# split2.net
KiCad netlist of a schematic drawn in Altium Designer
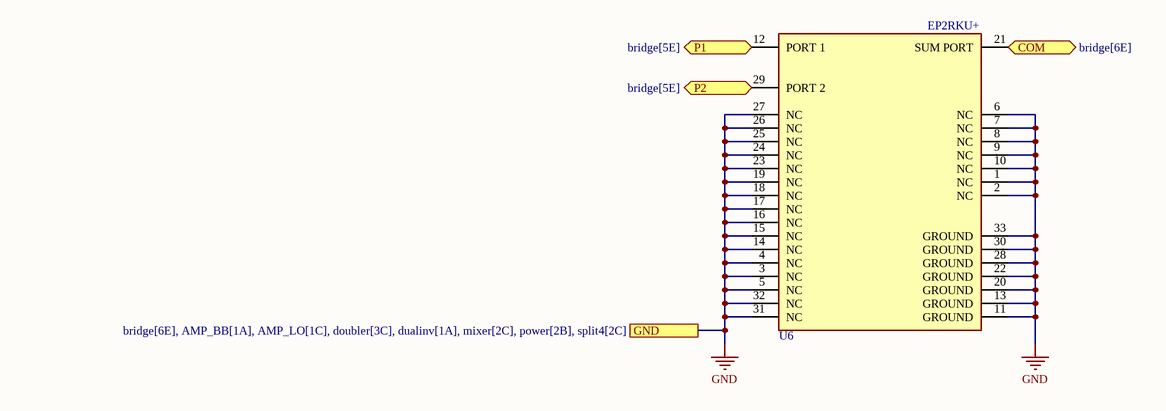
[diagram p0: split2.SchDoc]

(export (version "E")
  (design (tool "Eeschema 10.0.6"))
  (components
    (comp (ref "U6")
      (value "EP2RKU+")
      (footprint "EP2RKU+")
      (description "2 Ways MMIC Power Splitter, DC - 18000 MHz, 50Ω")
      (fields (field (name "MANUFACTURER") "Mini-Circuits"))
      (libsource (lib "FullyDigital") (part "EP2RKU+"))
    )
  )
  (nets
    (net (code "1") (name "/COM") (class "Default")
      (node (ref "U6") (pin "21") (pinfunction "SUM_PORT_21") (pintype "passive"))
    )
    (net (code "2") (name "/P1") (class "Default")
      (node (ref "U6") (pin "12") (pinfunction "PORT_1_12") (pintype "passive"))
    )
    (net (code "3") (name "/P2") (class "Default")
      (node (ref "U6") (pin "29") (pinfunction "PORT_2_29") (pintype "passive"))
    )
    (net (code "4") (name "GND") (class "Default")
      (node (ref "U6") (pin "1") (pinfunction "NC_1") (pintype "passive"))
      (node (ref "U6") (pin "10") (pinfunction "NC_10") (pintype "passive"))
      (node (ref "U6") (pin "11") (pinfunction "GROUND_11") (pintype "power_in"))
      (node (ref "U6") (pin "13") (pinfunction "GROUND_13") (pintype "power_in"))
      (node (ref "U6") (pin "14") (pinfunction "NC_14") (pintype "passive"))
      (node (ref "U6") (pin "15") (pinfunction "NC_15") (pintype "passive"))
      (node (ref "U6") (pin "16") (pinfunction "NC_16") (pintype "passive"))
      (node (ref "U6") (pin "17") (pinfunction "NC_17") (pintype "passive"))
      (node (ref "U6") (pin "18") (pinfunction "NC_18") (pintype "passive"))
      (node (ref "U6") (pin "19") (pinfunction "NC_19") (pintype "passive"))
      (node (ref "U6") (pin "2") (pinfunction "NC_2") (pintype "passive"))
      (node (ref "U6") (pin "20") (pinfunction "GROUND_20") (pintype "power_in"))
      (node (ref "U6") (pin "22") (pinfunction "GROUND_22") (pintype "power_in"))
      (node (ref "U6") (pin "23") (pinfunction "NC_23") (pintype "passive"))
      (node (ref "U6") (pin "24") (pinfunction "NC_24") (pintype "passive"))
      (node (ref "U6") (pin "25") (pinfunction "NC_25") (pintype "passive"))
      (node (ref "U6") (pin "26") (pinfunction "NC_26") (pintype "passive"))
      (node (ref "U6") (pin "27") (pinfunction "NC_27") (pintype "passive"))
      (node (ref "U6") (pin "28") (pinfunction "GROUND_28") (pintype "passive"))
      (node (ref "U6") (pin "3") (pinfunction "NC_3") (pintype "passive"))
      (node (ref "U6") (pin "30") (pinfunction "GROUND_30") (pintype "power_in"))
      (node (ref "U6") (pin "31") (pinfunction "NC_31") (pintype "passive"))
      (node (ref "U6") (pin "32") (pinfunction "NC_32") (pintype "passive"))
      (node (ref "U6") (pin "33") (pinfunction "GROUND_33") (pintype "power_in"))
      (node (ref "U6") (pin "4") (pinfunction "NC_4") (pintype "passive"))
      (node (ref "U6") (pin "5") (pinfunction "NC_5") (pintype "passive"))
      (node (ref "U6") (pin "6") (pinfunction "NC_6") (pintype "passive"))
      (node (ref "U6") (pin "7") (pinfunction "NC_7") (pintype "passive"))
      (node (ref "U6") (pin "8") (pinfunction "NC_8") (pintype "passive"))
      (node (ref "U6") (pin "9") (pinfunction "NC_9") (pintype "passive"))
    )
  )
)
